# Test_Schematic.net
KiCad netlist of a schematic drawn in EAGLE
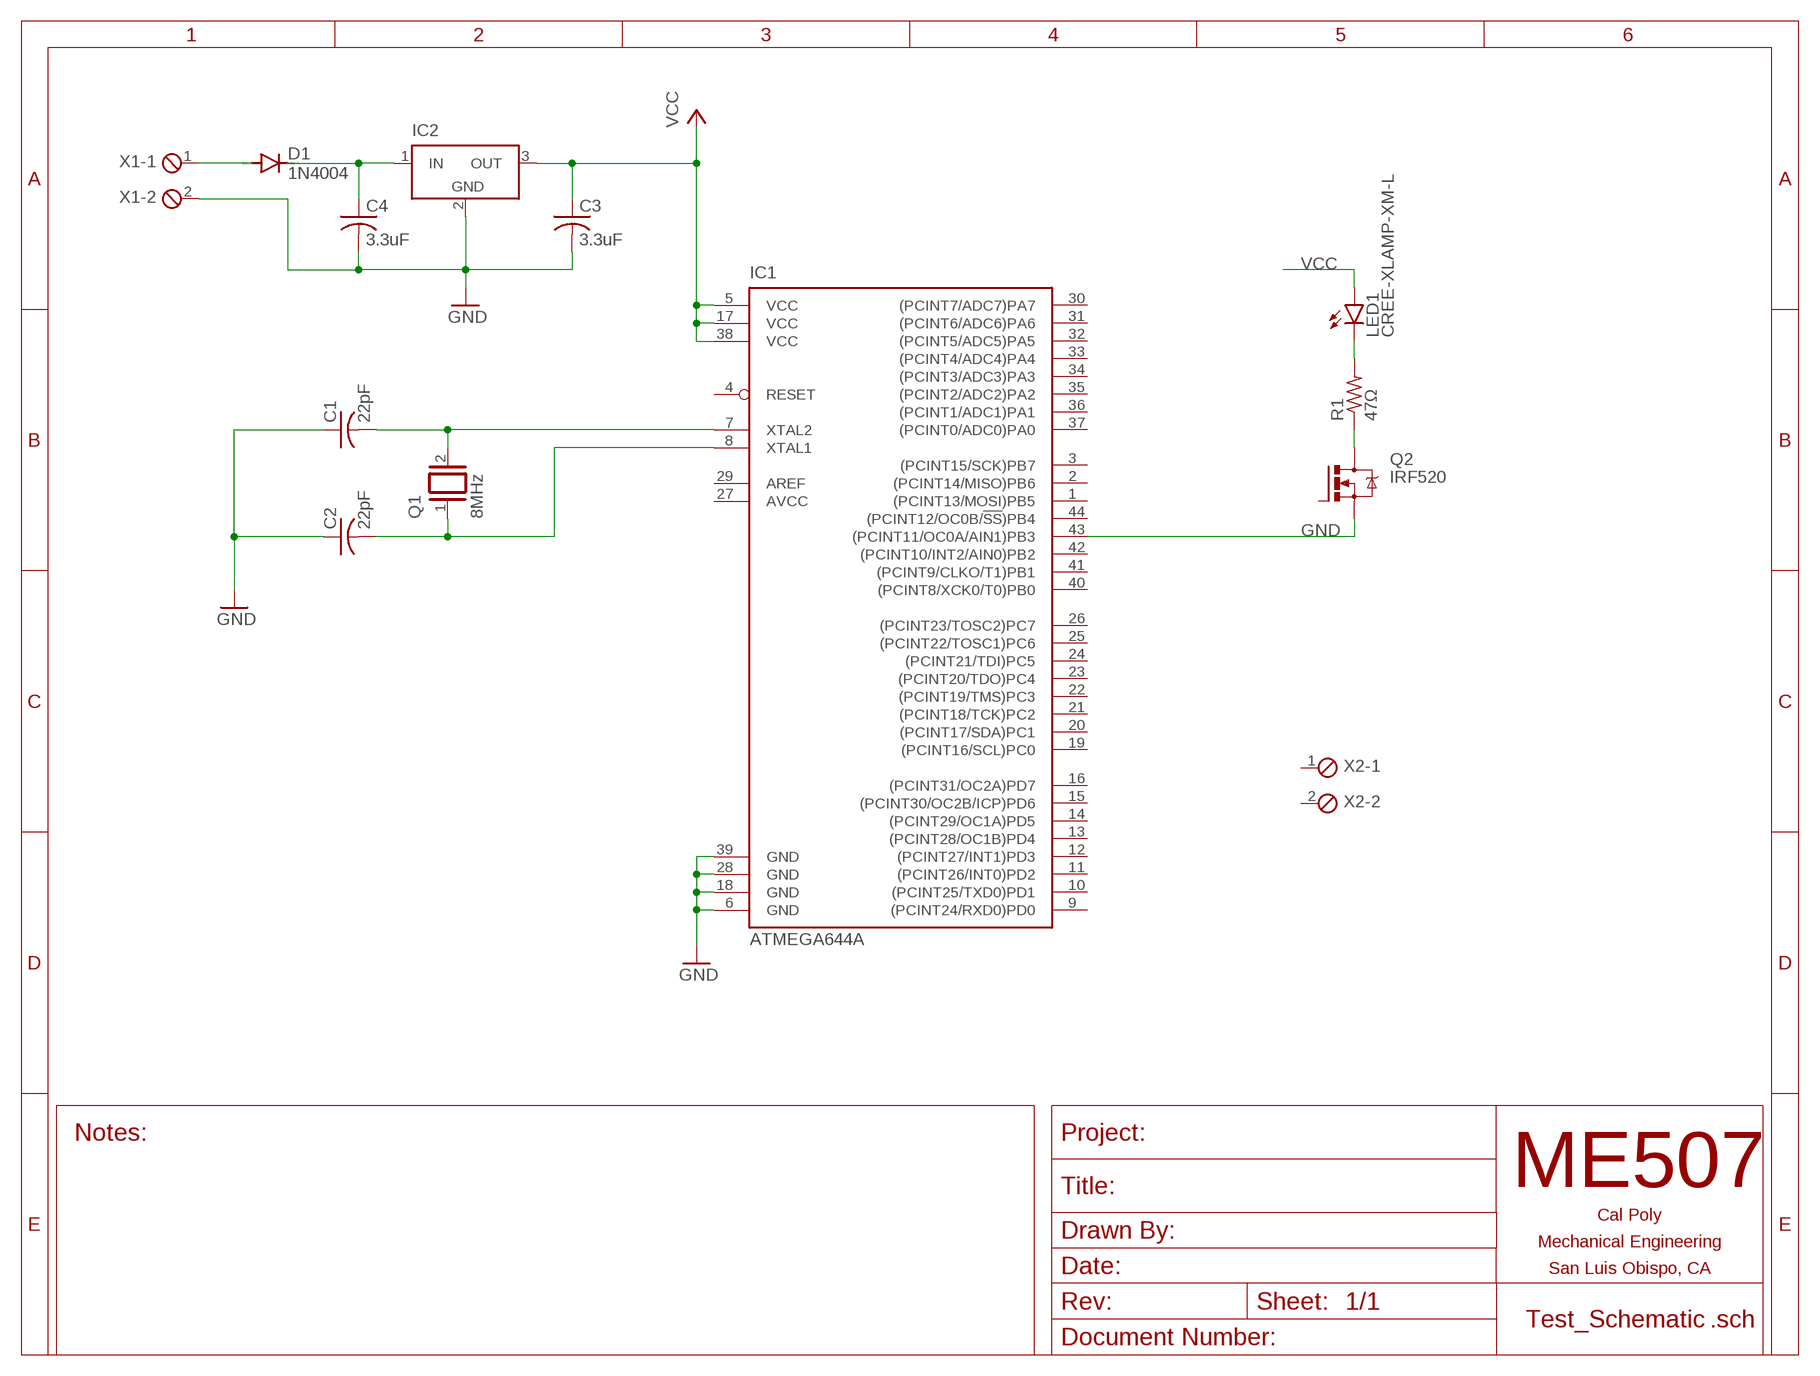
[diagram p0: schematic, sheet 1]

(export (version "E")
  (design (tool "Eeschema 10.0.6"))
  (components
    (comp (ref "C1")
      (value "22pF")
      (footprint "eagle-import:C0805")
      (libsource (lib "eagle-import") (part "C-USC0805"))
    )
    (comp (ref "C2")
      (value "22pF")
      (footprint "eagle-import:C0805")
      (libsource (lib "eagle-import") (part "C-USC0805"))
    )
    (comp (ref "C3")
      (value "3.3uF")
      (footprint "eagle-import:C0805")
      (libsource (lib "eagle-import") (part "C-USC0805"))
    )
    (comp (ref "C4")
      (value "3.3uF")
      (footprint "eagle-import:C0805")
      (libsource (lib "eagle-import") (part "C-USC0805"))
    )
    (comp (ref "D1")
      (value "1N4004")
      (footprint "eagle-import:DO41-10")
      (libsource (lib "eagle-import") (part "1N4004"))
    )
    (comp (ref "IC1")
      (value "ATMEGA644A")
      (footprint "eagle-import:TQFP44")
      (fields (field (name "MPN") "ATMEGA644PV-10AU"))
      (libsource (lib "eagle-import") (part "ATMEGA644A"))
    )
    (comp (ref "IC2")
      (value "LT1129CST5")
      (footprint "eagle-import:SOT223")
      (fields (field (name "MPN") "LT1129CST-5#PBF"))
      (libsource (lib "eagle-import") (part "LT1129CST5"))
    )
    (comp (ref "LED1")
      (value "CREE-XLAMP-XM-L")
      (footprint "eagle-import:CREE-XLAMP-XM-L")
      (libsource (lib "eagle-import") (part "CREE-XLAMP-XM-L"))
    )
    (comp (ref "Q1")
      (value "8MHz")
      (footprint "eagle-import:QS")
      (libsource (lib "eagle-import") (part "XTAL/S"))
    )
    (comp (ref "Q2")
      (value "IRF520")
      (footprint "eagle-import:TO220BV")
      (libsource (lib "eagle-import") (part "IRF520"))
    )
    (comp (ref "R1")
      (value "47Ω")
      (footprint "eagle-import:0309V")
      (libsource (lib "eagle-import") (part "R-US_0309/V"))
    )
    (comp (ref "X1")
      (value "SCREWTERM_2P_254")
      (footprint "eagle-import:2POL254")
      (libsource (lib "eagle-import") (part "SCREWTERM_2P_254"))
    )
    (comp (ref "X2")
      (value "SCREWTERM_2P_254")
      (footprint "eagle-import:2POL254")
      (libsource (lib "eagle-import") (part "SCREWTERM_2P_254"))
    )
  )
  (nets
    (net (code "1") (name "/AVCC") (class "Default")
      (node (ref "IC1") (pin "27") (pinfunction "AVCC_27") (pintype "power_in"))
    )
    (net (code "2") (name "GND") (class "Default")
      (node (ref "C1") (pin "1") (pinfunction "1_1") (pintype "passive"))
      (node (ref "C2") (pin "1") (pinfunction "1_1") (pintype "passive"))
      (node (ref "C3") (pin "2") (pinfunction "2_2") (pintype "passive"))
      (node (ref "C4") (pin "2") (pinfunction "2_2") (pintype "passive"))
      (node (ref "IC1") (pin "18") (pinfunction "GND_18") (pintype "power_in"))
      (node (ref "IC1") (pin "28") (pinfunction "GND_28") (pintype "power_in"))
      (node (ref "IC1") (pin "39") (pinfunction "GND_39") (pintype "power_in"))
      (node (ref "IC1") (pin "43") (pinfunction "(PCINT11/OC0A/AIN1)PB3_43") (pintype "bidirectional"))
      (node (ref "IC1") (pin "6") (pinfunction "GND_6") (pintype "power_in"))
      (node (ref "IC2") (pin "2") (pinfunction "GND_2") (pintype "power_in"))
      (node (ref "Q2") (pin "S") (pinfunction "S_S") (pintype "passive"))
      (node (ref "X1") (pin "2") (pinfunction "1_2") (pintype "passive"))
    )
    (net (code "3") (name "Net-(D1-PadA)") (class "Default")
      (node (ref "D1") (pin "A") (pinfunction "A_A") (pintype "passive"))
      (node (ref "X1") (pin "1") (pinfunction "1_1") (pintype "passive"))
    )
    (net (code "4") (name "Net-(IC1-XTAL1)") (class "Default")
      (node (ref "C2") (pin "2") (pinfunction "2_2") (pintype "passive"))
      (node (ref "IC1") (pin "8") (pinfunction "XTAL1_8") (pintype "bidirectional"))
      (node (ref "Q1") (pin "1") (pinfunction "1_1") (pintype "passive"))
    )
    (net (code "5") (name "Net-(IC1-XTAL2)") (class "Default")
      (node (ref "C1") (pin "2") (pinfunction "2_2") (pintype "passive"))
      (node (ref "IC1") (pin "7") (pinfunction "XTAL2_7") (pintype "bidirectional"))
      (node (ref "Q1") (pin "2") (pinfunction "2_2") (pintype "passive"))
    )
    (net (code "6") (name "Net-(IC2A-IN)") (class "Default")
      (node (ref "C4") (pin "1") (pinfunction "1_1") (pintype "passive"))
      (node (ref "D1") (pin "C") (pinfunction "C_C") (pintype "passive"))
      (node (ref "IC2") (pin "1") (pinfunction "IN_1") (pintype "input"))
    )
    (net (code "7") (name "Net-(LED1-C-PadC@1)") (class "Default")
      (node (ref "LED1") (pin "C") (pinfunction "C_C") (pintype "passive"))
      (node (ref "LED1") (pin "C@1") (pinfunction "C_C@1") (pintype "passive"))
      (node (ref "R1") (pin "2") (pinfunction "2_2") (pintype "passive"))
    )
    (net (code "8") (name "Net-(Q2-PadD)") (class "Default")
      (node (ref "Q2") (pin "D") (pinfunction "D_D") (pintype "passive"))
      (node (ref "R1") (pin "1") (pinfunction "1_1") (pintype "passive"))
    )
    (net (code "9") (name "VCC") (class "Default")
      (node (ref "C3") (pin "1") (pinfunction "1_1") (pintype "passive"))
      (node (ref "IC1") (pin "17") (pinfunction "VCC_17") (pintype "power_in"))
      (node (ref "IC1") (pin "38") (pinfunction "VCC_38") (pintype "power_in"))
      (node (ref "IC1") (pin "5") (pinfunction "VCC_5") (pintype "power_in"))
      (node (ref "IC2") (pin "3") (pinfunction "OUT_3") (pintype "output"))
      (node (ref "LED1") (pin "A") (pinfunction "A_A") (pintype "passive"))
      (node (ref "LED1") (pin "A@1") (pinfunction "A_A@1") (pintype "passive"))
    )
    (net (code "10") (name "unconnected-(IC1-(PCINT0{slash}ADC0)PA0-Pad37)") (class "Default")
      (node (ref "IC1") (pin "37") (pinfunction "(PCINT0/ADC0)PA0_37") (pintype "bidirectional"))
    )
    (net (code "11") (name "unconnected-(IC1-(PCINT1{slash}ADC1)PA1-Pad36)") (class "Default")
      (node (ref "IC1") (pin "36") (pinfunction "(PCINT1/ADC1)PA1_36") (pintype "bidirectional"))
    )
    (net (code "12") (name "unconnected-(IC1-(PCINT2{slash}ADC2)PA2-Pad35)") (class "Default")
      (node (ref "IC1") (pin "35") (pinfunction "(PCINT2/ADC2)PA2_35") (pintype "bidirectional"))
    )
    (net (code "13") (name "unconnected-(IC1-(PCINT3{slash}ADC3)PA3-Pad34)") (class "Default")
      (node (ref "IC1") (pin "34") (pinfunction "(PCINT3/ADC3)PA3_34") (pintype "bidirectional"))
    )
    (net (code "14") (name "unconnected-(IC1-(PCINT4{slash}ADC4)PA4-Pad33)") (class "Default")
      (node (ref "IC1") (pin "33") (pinfunction "(PCINT4/ADC4)PA4_33") (pintype "bidirectional"))
    )
    (net (code "15") (name "unconnected-(IC1-(PCINT5{slash}ADC5)PA5-Pad32)") (class "Default")
      (node (ref "IC1") (pin "32") (pinfunction "(PCINT5/ADC5)PA5_32") (pintype "bidirectional"))
    )
    (net (code "16") (name "unconnected-(IC1-(PCINT6{slash}ADC6)PA6-Pad31)") (class "Default")
      (node (ref "IC1") (pin "31") (pinfunction "(PCINT6/ADC6)PA6_31") (pintype "bidirectional"))
    )
    (net (code "17") (name "unconnected-(IC1-(PCINT7{slash}ADC7)PA7-Pad30)") (class "Default")
      (node (ref "IC1") (pin "30") (pinfunction "(PCINT7/ADC7)PA7_30") (pintype "bidirectional"))
    )
    (net (code "18") (name "unconnected-(IC1-(PCINT8{slash}XCK0{slash}T0)PB0-Pad40)") (class "Default")
      (node (ref "IC1") (pin "40") (pinfunction "(PCINT8/XCK0/T0)PB0_40") (pintype "bidirectional"))
    )
    (net (code "19") (name "unconnected-(IC1-(PCINT9{slash}CLKO{slash}T1)PB1-Pad41)") (class "Default")
      (node (ref "IC1") (pin "41") (pinfunction "(PCINT9/CLKO/T1)PB1_41") (pintype "bidirectional"))
    )
    (net (code "20") (name "unconnected-(IC1-(PCINT10{slash}INT2{slash}AIN0)PB2-Pad42)") (class "Default")
      (node (ref "IC1") (pin "42") (pinfunction "(PCINT10/INT2/AIN0)PB2_42") (pintype "bidirectional"))
    )
    (net (code "21") (name "unconnected-(IC1-(PCINT12{slash}OC0B{slash}~{SS})PB4-Pad44)") (class "Default")
      (node (ref "IC1") (pin "44") (pinfunction "(PCINT12/OC0B/~{SS})PB4_44") (pintype "bidirectional"))
    )
    (net (code "22") (name "unconnected-(IC1-(PCINT13{slash}MOSI)PB5-Pad1)") (class "Default")
      (node (ref "IC1") (pin "1") (pinfunction "(PCINT13/MOSI)PB5_1") (pintype "bidirectional"))
    )
    (net (code "23") (name "unconnected-(IC1-(PCINT14{slash}MISO)PB6-Pad2)") (class "Default")
      (node (ref "IC1") (pin "2") (pinfunction "(PCINT14/MISO)PB6_2") (pintype "bidirectional"))
    )
    (net (code "24") (name "unconnected-(IC1-(PCINT15{slash}SCK)PB7-Pad3)") (class "Default")
      (node (ref "IC1") (pin "3") (pinfunction "(PCINT15/SCK)PB7_3") (pintype "bidirectional"))
    )
    (net (code "25") (name "unconnected-(IC1-(PCINT16{slash}SCL)PC0-Pad19)") (class "Default")
      (node (ref "IC1") (pin "19") (pinfunction "(PCINT16/SCL)PC0_19") (pintype "output"))
    )
    (net (code "26") (name "unconnected-(IC1-(PCINT17{slash}SDA)PC1-Pad20)") (class "Default")
      (node (ref "IC1") (pin "20") (pinfunction "(PCINT17/SDA)PC1_20") (pintype "output"))
    )
    (net (code "27") (name "unconnected-(IC1-(PCINT18{slash}TCK)PC2-Pad21)") (class "Default")
      (node (ref "IC1") (pin "21") (pinfunction "(PCINT18/TCK)PC2_21") (pintype "output"))
    )
    (net (code "28") (name "unconnected-(IC1-(PCINT19{slash}TMS)PC3-Pad22)") (class "Default")
      (node (ref "IC1") (pin "22") (pinfunction "(PCINT19/TMS)PC3_22") (pintype "output"))
    )
    (net (code "29") (name "unconnected-(IC1-(PCINT20{slash}TDO)PC4-Pad23)") (class "Default")
      (node (ref "IC1") (pin "23") (pinfunction "(PCINT20/TDO)PC4_23") (pintype "output"))
    )
    (net (code "30") (name "unconnected-(IC1-(PCINT21{slash}TDI)PC5-Pad24)") (class "Default")
      (node (ref "IC1") (pin "24") (pinfunction "(PCINT21/TDI)PC5_24") (pintype "output"))
    )
    (net (code "31") (name "unconnected-(IC1-(PCINT22{slash}TOSC1)PC6-Pad25)") (class "Default")
      (node (ref "IC1") (pin "25") (pinfunction "(PCINT22/TOSC1)PC6_25") (pintype "output"))
    )
    (net (code "32") (name "unconnected-(IC1-(PCINT23{slash}TOSC2)PC7-Pad26)") (class "Default")
      (node (ref "IC1") (pin "26") (pinfunction "(PCINT23/TOSC2)PC7_26") (pintype "output"))
    )
    (net (code "33") (name "unconnected-(IC1-(PCINT24{slash}RXD0)PD0-Pad9)") (class "Default")
      (node (ref "IC1") (pin "9") (pinfunction "(PCINT24/RXD0)PD0_9") (pintype "bidirectional"))
    )
    (net (code "34") (name "unconnected-(IC1-(PCINT25{slash}TXD0)PD1-Pad10)") (class "Default")
      (node (ref "IC1") (pin "10") (pinfunction "(PCINT25/TXD0)PD1_10") (pintype "bidirectional"))
    )
    (net (code "35") (name "unconnected-(IC1-(PCINT26{slash}INT0)PD2-Pad11)") (class "Default")
      (node (ref "IC1") (pin "11") (pinfunction "(PCINT26/INT0)PD2_11") (pintype "bidirectional"))
    )
    (net (code "36") (name "unconnected-(IC1-(PCINT27{slash}INT1)PD3-Pad12)") (class "Default")
      (node (ref "IC1") (pin "12") (pinfunction "(PCINT27/INT1)PD3_12") (pintype "bidirectional"))
    )
    (net (code "37") (name "unconnected-(IC1-(PCINT28{slash}OC1B)PD4-Pad13)") (class "Default")
      (node (ref "IC1") (pin "13") (pinfunction "(PCINT28/OC1B)PD4_13") (pintype "bidirectional"))
    )
    (net (code "38") (name "unconnected-(IC1-(PCINT29{slash}OC1A)PD5-Pad14)") (class "Default")
      (node (ref "IC1") (pin "14") (pinfunction "(PCINT29/OC1A)PD5_14") (pintype "bidirectional"))
    )
    (net (code "39") (name "unconnected-(IC1-(PCINT30{slash}OC2B{slash}ICP)PD6-Pad15)") (class "Default")
      (node (ref "IC1") (pin "15") (pinfunction "(PCINT30/OC2B/ICP)PD6_15") (pintype "bidirectional"))
    )
    (net (code "40") (name "unconnected-(IC1-(PCINT31{slash}OC2A)PD7-Pad16)") (class "Default")
      (node (ref "IC1") (pin "16") (pinfunction "(PCINT31/OC2A)PD7_16") (pintype "bidirectional"))
    )
    (net (code "41") (name "unconnected-(IC1-AREF-Pad29)") (class "Default")
      (node (ref "IC1") (pin "29") (pinfunction "AREF_29") (pintype "passive"))
    )
    (net (code "42") (name "unconnected-(IC1-RESET-Pad4)") (class "Default")
      (node (ref "IC1") (pin "4") (pinfunction "RESET_4") (pintype "input"))
    )
    (net (code "43") (name "unconnected-(Q2-PadG)") (class "Default")
      (node (ref "Q2") (pin "G") (pinfunction "G_G") (pintype "passive"))
    )
    (net (code "44") (name "unconnected-(X2-Pad1)") (class "Default")
      (node (ref "X2") (pin "1") (pinfunction "1_1") (pintype "passive"))
    )
    (net (code "45") (name "unconnected-(X2B-1-Pad2)") (class "Default")
      (node (ref "X2") (pin "2") (pinfunction "1_2") (pintype "passive"))
    )
  )
)
